# drawdio.net
KiCad netlist of a schematic drawn in EAGLE
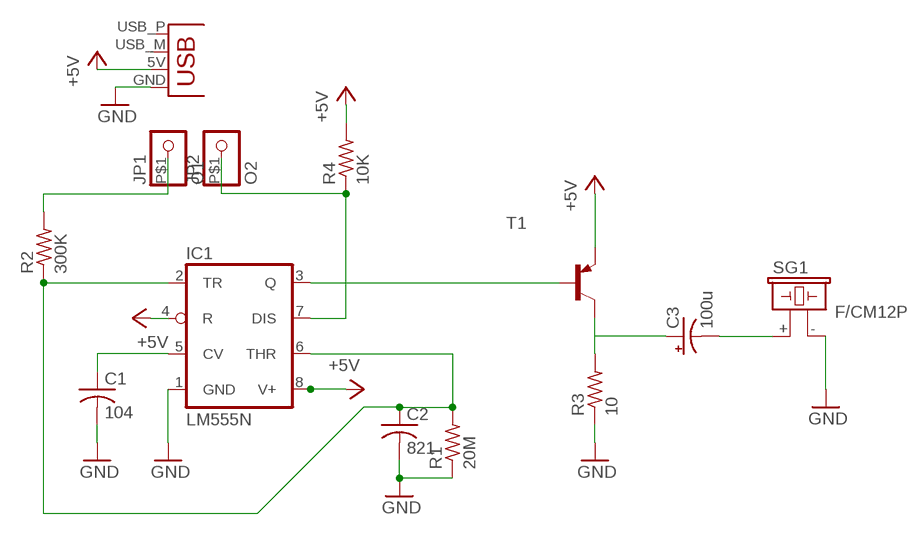
[diagram p0: schematic, sheet 1]

(export (version "E")
  (design (tool "Eeschema 10.0.6"))
  (components
    (comp (ref "C1")
      (value "104")
      (footprint "eagle-import:C025-030X050")
      (libsource (lib "eagle-import") (part "C-US025-030X050"))
    )
    (comp (ref "C2")
      (value "821")
      (footprint "eagle-import:C050-024X044")
      (libsource (lib "eagle-import") (part "C-US050-024X044"))
    )
    (comp (ref "C3")
      (value "100u")
      (footprint "eagle-import:E2,5-6E")
      (libsource (lib "eagle-import") (part "CPOL-USE2,5-6E"))
    )
    (comp (ref "IC1")
      (value "LM555N")
      (footprint "eagle-import:DIL08")
      (libsource (lib "eagle-import") (part "555NLM"))
    )
    (comp (ref "JP1")
      (value "O1")
      (footprint "eagle-import:1X1-BIGPOGO")
      (libsource (lib "eagle-import") (part "PINHD-1X1-BIGPOGO"))
    )
    (comp (ref "JP2")
      (value "O2")
      (footprint "eagle-import:1X1-BIGPOGO")
      (libsource (lib "eagle-import") (part "PINHD-1X1-BIGPOGO"))
    )
    (comp (ref "R1")
      (value "20M")
      (footprint "eagle-import:0207_7")
      (libsource (lib "eagle-import") (part "R-US_0207/7"))
    )
    (comp (ref "R2")
      (value "300K")
      (footprint "eagle-import:0207_7")
      (libsource (lib "eagle-import") (part "R-US_0207/7"))
    )
    (comp (ref "R3")
      (value "10")
      (footprint "eagle-import:0207_7")
      (libsource (lib "eagle-import") (part "R-US_0207/7"))
    )
    (comp (ref "R4")
      (value "10K")
      (footprint "eagle-import:0207_7")
      (libsource (lib "eagle-import") (part "R-US_0207/7"))
    )
    (comp (ref "SG1")
      (value "F/CM12P")
      (footprint "eagle-import:F_CM12P")
      (libsource (lib "eagle-import") (part "F/CM12P"))
    )
    (comp (ref "T1")
      (value "MPS2907A-PNP-TO92-CBE")
      (footprint "eagle-import:TO92-CBE")
      (libsource (lib "eagle-import") (part "-PNP-TO92-CBEMPS2907A"))
    )
    (comp (ref "X1")
      (value "USBPCB")
      (footprint "eagle-import:USB-A-PCB")
      (libsource (lib "eagle-import") (part "USBPCB"))
    )
  )
  (nets
    (net (code "1") (name "+5V") (class "Default")
      (node (ref "IC1") (pin "4") (pinfunction "R_4") (pintype "input"))
      (node (ref "IC1") (pin "8") (pinfunction "V+_8") (pintype "power_in"))
      (node (ref "R4") (pin "2") (pinfunction "2_2") (pintype "passive"))
      (node (ref "T1") (pin "E") (pinfunction "E_E") (pintype "passive"))
      (node (ref "X1") (pin "5V") (pinfunction "VBUS_5V") (pintype "bidirectional"))
    )
    (net (code "2") (name "GND") (class "Default")
      (node (ref "C1") (pin "2") (pinfunction "2_2") (pintype "passive"))
      (node (ref "C2") (pin "2") (pinfunction "2_2") (pintype "passive"))
      (node (ref "IC1") (pin "1") (pinfunction "GND_1") (pintype "power_in"))
      (node (ref "R1") (pin "1") (pinfunction "1_1") (pintype "passive"))
      (node (ref "R3") (pin "1") (pinfunction "1_1") (pintype "passive"))
      (node (ref "SG1") (pin "-") (pinfunction "2_-") (pintype "passive"))
      (node (ref "X1") (pin "GND") (pinfunction "GND_GND") (pintype "bidirectional"))
    )
    (net (code "3") (name "Net-(C3-Pad+)") (class "Default")
      (node (ref "C3") (pin "+") (pinfunction "+_+") (pintype "passive"))
      (node (ref "R3") (pin "2") (pinfunction "2_2") (pintype "passive"))
      (node (ref "T1") (pin "C") (pinfunction "C_C") (pintype "passive"))
    )
    (net (code "4") (name "Net-(IC1-CV)") (class "Default")
      (node (ref "C1") (pin "1") (pinfunction "1_1") (pintype "passive"))
      (node (ref "IC1") (pin "5") (pinfunction "CV_5") (pintype "input"))
    )
    (net (code "5") (name "Net-(IC1-DIS)") (class "Default")
      (node (ref "IC1") (pin "7") (pinfunction "DIS_7") (pintype "input"))
      (node (ref "JP2") (pin "P$1") (pinfunction "1_P$1") (pintype "passive"))
      (node (ref "R4") (pin "1") (pinfunction "1_1") (pintype "passive"))
    )
    (net (code "6") (name "Net-(IC1-Q)") (class "Default")
      (node (ref "IC1") (pin "3") (pinfunction "Q_3") (pintype "output"))
      (node (ref "T1") (pin "B") (pinfunction "B_B") (pintype "passive"))
    )
    (net (code "7") (name "Net-(IC1-THR)") (class "Default")
      (node (ref "C2") (pin "1") (pinfunction "1_1") (pintype "passive"))
      (node (ref "IC1") (pin "2") (pinfunction "TR_2") (pintype "input"))
      (node (ref "IC1") (pin "6") (pinfunction "THR_6") (pintype "input"))
      (node (ref "R1") (pin "2") (pinfunction "2_2") (pintype "passive"))
      (node (ref "R2") (pin "1") (pinfunction "1_1") (pintype "passive"))
    )
    (net (code "8") (name "Net-(JP1-1)") (class "Default")
      (node (ref "JP1") (pin "P$1") (pinfunction "1_P$1") (pintype "passive"))
      (node (ref "R2") (pin "2") (pinfunction "2_2") (pintype "passive"))
    )
    (net (code "9") (name "Net-(SG1-1)") (class "Default")
      (node (ref "C3") (pin "-") (pinfunction "-_-") (pintype "passive"))
      (node (ref "SG1") (pin "+") (pinfunction "1_+") (pintype "passive"))
    )
    (net (code "10") (name "unconnected-(X1-D+-PadUSB_P)") (class "Default")
      (node (ref "X1") (pin "USB_P") (pinfunction "D+_USB_P") (pintype "bidirectional"))
    )
    (net (code "11") (name "unconnected-(X1-D--PadUSB_M)") (class "Default")
      (node (ref "X1") (pin "USB_M") (pinfunction "D-_USB_M") (pintype "bidirectional"))
    )
  )
)
